# 04C-10.net
KiCad netlist of a schematic drawn in EAGLE
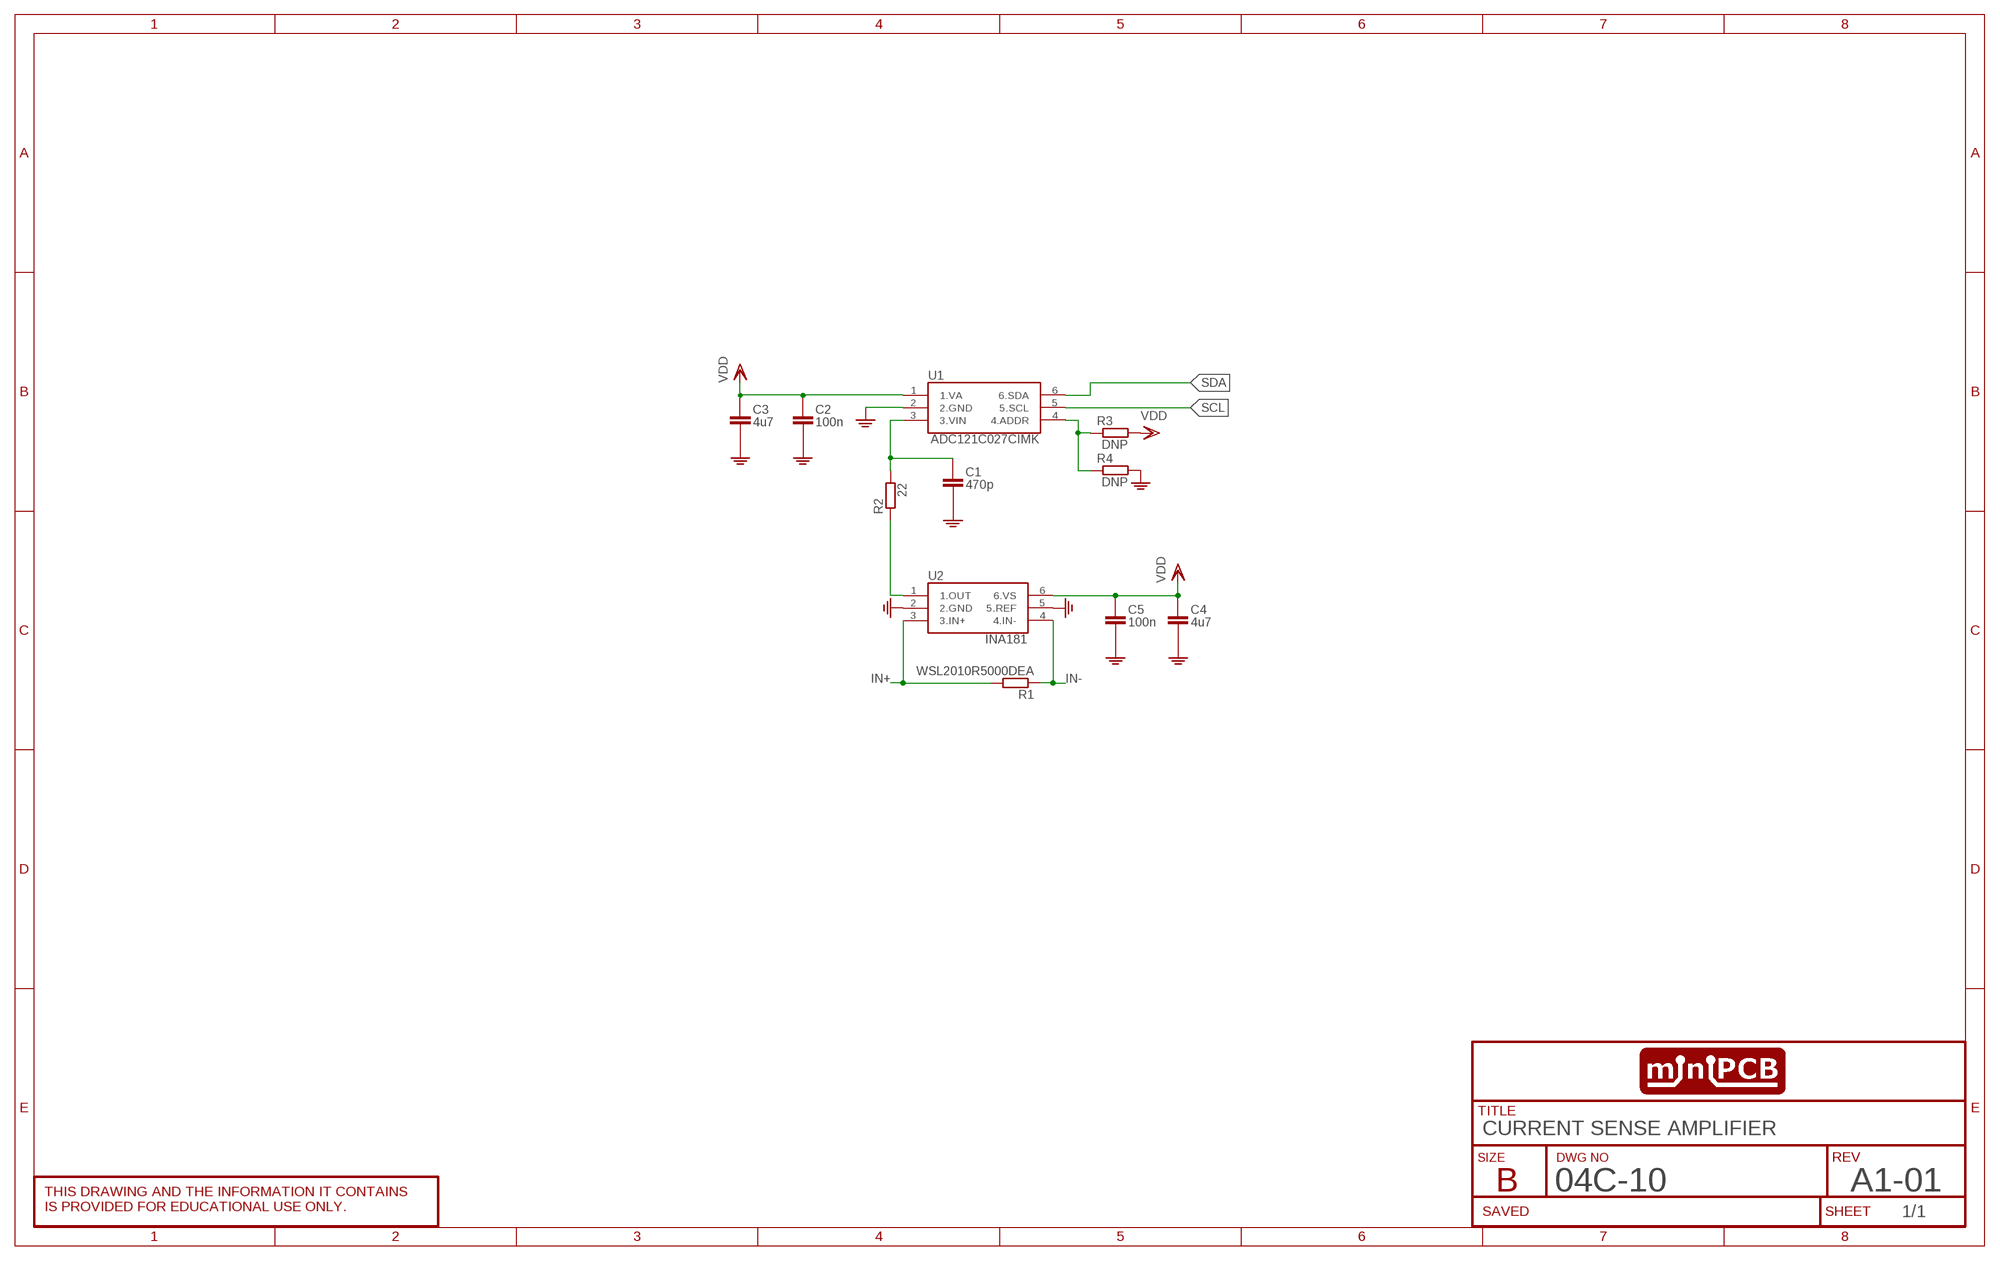
[diagram p0: schematic, sheet 1]

(export (version "E")
  (design (tool "Eeschema 10.0.6"))
  (components
    (comp (ref "C1")
      (value "470p")
      (footprint "eagle-import:C0402")
      (libsource (lib "eagle-import") (part "CAPACITOR0402"))
    )
    (comp (ref "C2")
      (value "100n")
      (footprint "eagle-import:C0402")
      (libsource (lib "eagle-import") (part "CAPACITOR0402"))
    )
    (comp (ref "C3")
      (value "4u7")
      (footprint "eagle-import:C0402")
      (libsource (lib "eagle-import") (part "CAPACITOR0402"))
    )
    (comp (ref "C4")
      (value "4u7")
      (footprint "eagle-import:C0402")
      (libsource (lib "eagle-import") (part "CAPACITOR0402"))
    )
    (comp (ref "C5")
      (value "100n")
      (footprint "eagle-import:C0402")
      (libsource (lib "eagle-import") (part "CAPACITOR0402"))
    )
    (comp (ref "R1")
      (value "WSL2010R5000DEA")
      (footprint "eagle-import:R5025")
      (libsource (lib "eagle-import") (part "R-EU_R5025"))
    )
    (comp (ref "R2")
      (value "22")
      (footprint "eagle-import:R0402")
      (libsource (lib "eagle-import") (part "RESISTOR0402"))
    )
    (comp (ref "R3")
      (value "DNP")
      (footprint "eagle-import:R0402")
      (libsource (lib "eagle-import") (part "RESISTOR0402"))
    )
    (comp (ref "R4")
      (value "DNP")
      (footprint "eagle-import:R0402")
      (libsource (lib "eagle-import") (part "RESISTOR0402"))
    )
    (comp (ref "U1")
      (value "ADC121C027CIMK")
      (footprint "eagle-import:SOT23-6")
      (libsource (lib "eagle-import") (part "ADC121C027CIMK"))
    )
    (comp (ref "U2")
      (value "INA181")
      (footprint "eagle-import:SOT23-6")
      (libsource (lib "eagle-import") (part "INAX81"))
    )
  )
  (nets
    (net (code "1") (name "/IN+") (class "Default")
      (node (ref "R1") (pin "2") (pinfunction "2_2") (pintype "passive"))
      (node (ref "U2") (pin "3") (pinfunction "3.IN+_3") (pintype "bidirectional"))
    )
    (net (code "2") (name "/IN-") (class "Default")
      (node (ref "R1") (pin "1") (pinfunction "1_1") (pintype "passive"))
      (node (ref "U2") (pin "4") (pinfunction "4.IN-_4") (pintype "bidirectional"))
    )
    (net (code "3") (name "GND") (class "Default")
      (node (ref "C1") (pin "2") (pinfunction "-_2") (pintype "passive"))
      (node (ref "C2") (pin "2") (pinfunction "-_2") (pintype "passive"))
      (node (ref "C3") (pin "2") (pinfunction "-_2") (pintype "passive"))
      (node (ref "C4") (pin "2") (pinfunction "-_2") (pintype "passive"))
      (node (ref "C5") (pin "2") (pinfunction "-_2") (pintype "passive"))
      (node (ref "R4") (pin "2") (pinfunction "2_2") (pintype "passive"))
      (node (ref "U1") (pin "2") (pinfunction "2.GND_2") (pintype "bidirectional"))
      (node (ref "U2") (pin "2") (pinfunction "2.GND_2") (pintype "bidirectional"))
      (node (ref "U2") (pin "5") (pinfunction "5.REF_5") (pintype "bidirectional"))
    )
    (net (code "4") (name "Net-(C1-+)") (class "Default")
      (node (ref "C1") (pin "1") (pinfunction "+_1") (pintype "passive"))
      (node (ref "R2") (pin "2") (pinfunction "2_2") (pintype "passive"))
      (node (ref "U1") (pin "3") (pinfunction "3.VIN_3") (pintype "bidirectional"))
    )
    (net (code "5") (name "Net-(U1-4.ADDR)") (class "Default")
      (node (ref "R3") (pin "1") (pinfunction "1_1") (pintype "passive"))
      (node (ref "R4") (pin "1") (pinfunction "1_1") (pintype "passive"))
      (node (ref "U1") (pin "4") (pinfunction "4.ADDR_4") (pintype "bidirectional"))
    )
    (net (code "6") (name "Net-(U2-1.OUT)") (class "Default")
      (node (ref "R2") (pin "1") (pinfunction "1_1") (pintype "passive"))
      (node (ref "U2") (pin "1") (pinfunction "1.OUT_1") (pintype "bidirectional"))
    )
    (net (code "7") (name "SCL") (class "Default")
      (node (ref "U1") (pin "5") (pinfunction "5.SCL_5") (pintype "bidirectional"))
    )
    (net (code "8") (name "SDA") (class "Default")
      (node (ref "U1") (pin "6") (pinfunction "6.SDA_6") (pintype "bidirectional"))
    )
    (net (code "9") (name "VDD") (class "Default")
      (node (ref "C2") (pin "1") (pinfunction "+_1") (pintype "passive"))
      (node (ref "C3") (pin "1") (pinfunction "+_1") (pintype "passive"))
      (node (ref "C4") (pin "1") (pinfunction "+_1") (pintype "passive"))
      (node (ref "C5") (pin "1") (pinfunction "+_1") (pintype "passive"))
      (node (ref "R3") (pin "2") (pinfunction "2_2") (pintype "passive"))
      (node (ref "U1") (pin "1") (pinfunction "1.VA_1") (pintype "bidirectional"))
      (node (ref "U2") (pin "6") (pinfunction "6.VS_6") (pintype "bidirectional"))
    )
  )
)
